# pc_rpi_healthypi.net
KiCad netlist of a schematic drawn in EAGLE
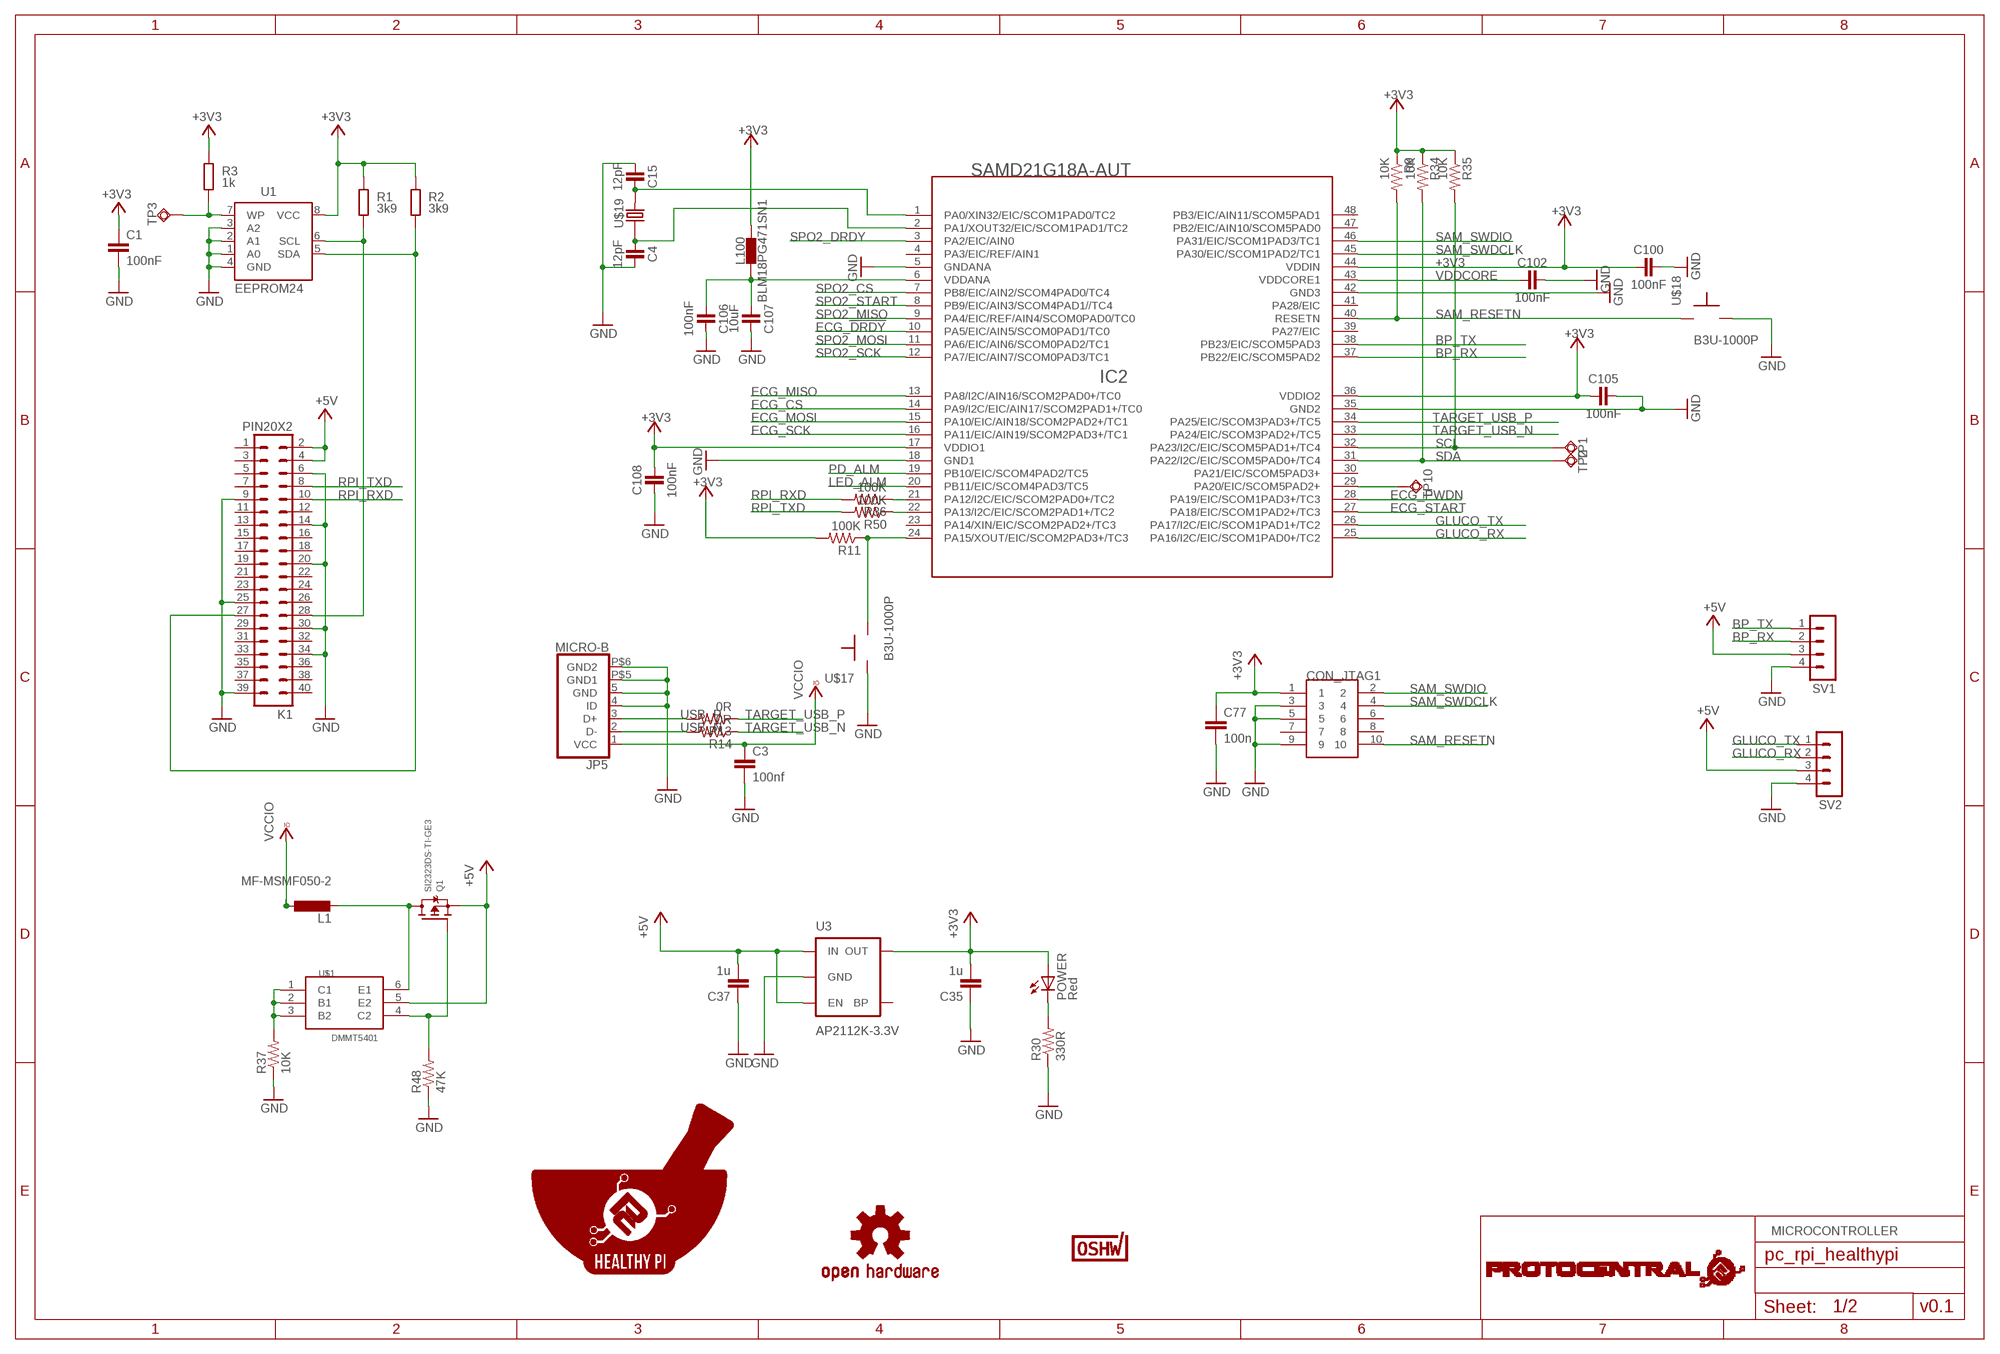
[diagram p0: schematic, sheet 1]
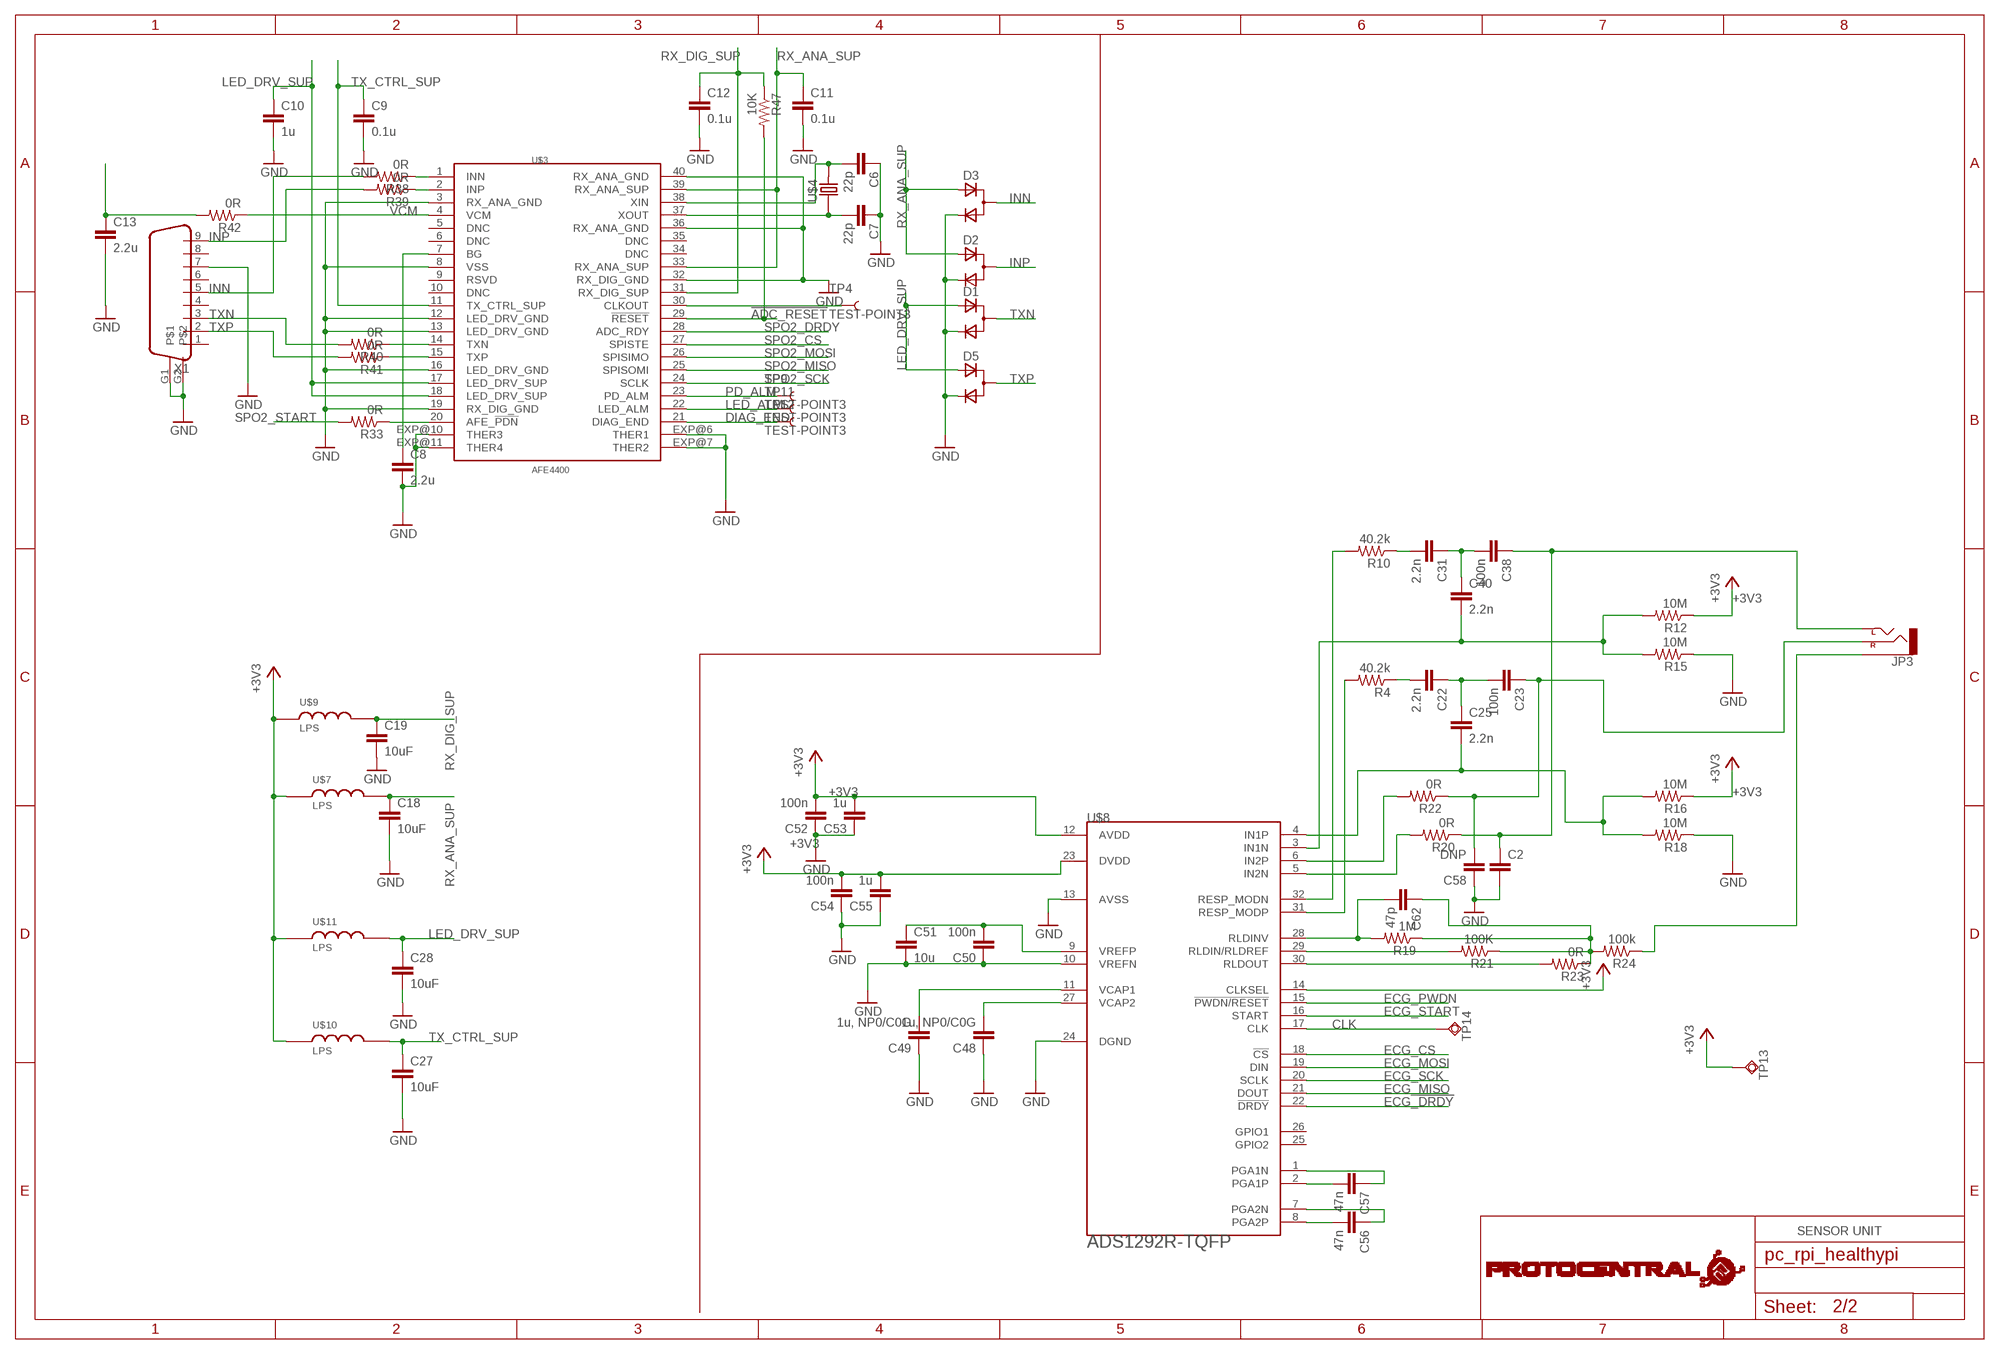
[diagram p1: schematic, sheet 2]

(export (version "E")
  (design (tool "Eeschema 10.0.6"))
  (components
    (comp (ref "C1")
      (value "100nF")
      (footprint "eagle-import:C0805K")
      (libsource (lib "eagle-import") (part "resistor_C-EUC0805K"))
    )
    (comp (ref "C3")
      (value "100nf")
      (footprint "eagle-import:C0402")
      (libsource (lib "eagle-import") (part "C-EUC0402"))
    )
    (comp (ref "C4")
      (value "12pF")
      (footprint "eagle-import:C0402")
      (libsource (lib "eagle-import") (part "CAPACITORS-0402"))
    )
    (comp (ref "C15")
      (value "12pF")
      (footprint "eagle-import:C0402")
      (libsource (lib "eagle-import") (part "CAPACITORS-0402"))
    )
    (comp (ref "C35")
      (value "1u")
      (footprint "eagle-import:C0402")
      (libsource (lib "eagle-import") (part "C-EUC0402"))
    )
    (comp (ref "C37")
      (value "1u")
      (footprint "eagle-import:C0402")
      (libsource (lib "eagle-import") (part "C-EUC0402"))
    )
    (comp (ref "C77")
      (value "100n")
      (footprint "eagle-import:C0805")
      (libsource (lib "eagle-import") (part "C-EUC0805"))
    )
    (comp (ref "C100")
      (value "100nF")
      (footprint "eagle-import:C0805")
      (libsource (lib "eagle-import") (part "CAPACITORS-0805"))
    )
    (comp (ref "C102")
      (value "100nF")
      (footprint "eagle-import:C0805")
      (libsource (lib "eagle-import") (part "CAPACITORS-0805"))
    )
    (comp (ref "C105")
      (value "100nF")
      (footprint "eagle-import:C0805")
      (libsource (lib "eagle-import") (part "CAPACITORS-0805"))
    )
    (comp (ref "C106")
      (value "100nF")
      (footprint "eagle-import:C0805")
      (libsource (lib "eagle-import") (part "CAPACITORS-0805"))
    )
    (comp (ref "C107")
      (value "10uF")
      (footprint "eagle-import:C0805")
      (libsource (lib "eagle-import") (part "CAPACITORS-0805"))
    )
    (comp (ref "C108")
      (value "100nF")
      (footprint "eagle-import:C0805")
      (libsource (lib "eagle-import") (part "CAPACITORS-0805"))
    )
    (comp (ref "CON_JTAG1")
      (value "HDR-SMT-50MIL/5X2")
      (footprint "eagle-import:HDR-SMT-50MIL_5X2")
      (libsource (lib "eagle-import") (part "HDR-SMT-50MIL/5X2"))
    )
    (comp (ref "IC2")
      (value "SAMD21G18A-AUT")
      (footprint "eagle-import:TQFP48")
      (libsource (lib "eagle-import") (part "SAMD21G18A"))
    )
    (comp (ref "JP5")
      (value "MICRO-B")
      (footprint "eagle-import:MICRO-B")
      (libsource (lib "eagle-import") (part "MICRO-B"))
    )
    (comp (ref "K1")
      (value "PIN20X2")
      (footprint "eagle-import:PIN_20X2")
      (libsource (lib "eagle-import") (part "PIN20X2"))
    )
    (comp (ref "L1")
      (value "MF-MSMF050-2")
      (footprint "eagle-import:L1812")
      (libsource (lib "eagle-import") (part "L-EUL1812"))
    )
    (comp (ref "L100")
      (value "BLM18PG471SN1")
      (footprint "eagle-import:C0603")
      (libsource (lib "eagle-import") (part "INDUCTOR-0603"))
    )
    (comp (ref "POWER")
      (value "Red")
      (footprint "eagle-import:CHIPLED_0603")
      (libsource (lib "eagle-import") (part "LEDCHIPLED_0603"))
    )
    (comp (ref "Q1")
      (value "SI2323DS-TI-GE3")
      (footprint "eagle-import:SOT23-R")
      (libsource (lib "eagle-import") (part "MOSFET-P"))
    )
    (comp (ref "R1")
      (value "3k9")
      (footprint "eagle-import:M0805")
      (fields (field (name "TOLERANCE") "5%"))
      (libsource (lib "eagle-import") (part "R-EU_M0805"))
    )
    (comp (ref "R2")
      (value "3k9")
      (footprint "eagle-import:M0805")
      (fields (field (name "TOLERANCE") "5%"))
      (libsource (lib "eagle-import") (part "R-EU_M0805"))
    )
    (comp (ref "R3")
      (value "1k")
      (footprint "eagle-import:M0805")
      (fields (field (name "TOLERANCE") "5%"))
      (libsource (lib "eagle-import") (part "R-EU_M0805"))
    )
    (comp (ref "R9")
      (value "10K")
      (footprint "eagle-import:R0805")
      (libsource (lib "eagle-import") (part "R-US_R0805"))
    )
    (comp (ref "R11")
      (value "100K")
      (footprint "eagle-import:R0805")
      (libsource (lib "eagle-import") (part "R-US_R0805"))
    )
    (comp (ref "R13")
      (value "0R")
      (footprint "eagle-import:R0402")
      (libsource (lib "eagle-import") (part "R-US_R0402"))
    )
    (comp (ref "R14")
      (value "0R")
      (footprint "eagle-import:R0402")
      (libsource (lib "eagle-import") (part "R-US_R0402"))
    )
    (comp (ref "R30")
      (value "330R")
      (footprint "eagle-import:R0402")
      (libsource (lib "eagle-import") (part "R-US_R0402"))
    )
    (comp (ref "R34")
      (value "10K")
      (footprint "eagle-import:R0805")
      (libsource (lib "eagle-import") (part "R-US_R0805"))
    )
    (comp (ref "R35")
      (value "10K")
      (footprint "eagle-import:R0805")
      (libsource (lib "eagle-import") (part "R-US_R0805"))
    )
    (comp (ref "R36")
      (value "100K")
      (footprint "eagle-import:R0402")
      (libsource (lib "eagle-import") (part "R-US_R0402"))
    )
    (comp (ref "R37")
      (value "10K")
      (footprint "eagle-import:R0805")
      (libsource (lib "eagle-import") (part "R-US_R0805"))
    )
    (comp (ref "R48")
      (value "47K")
      (footprint "eagle-import:R0805")
      (libsource (lib "eagle-import") (part "R-US_R0805"))
    )
    (comp (ref "R50")
      (value "100K")
      (footprint "eagle-import:R0402")
      (libsource (lib "eagle-import") (part "R-US_R0402"))
    )
    (comp (ref "SV1")
      (value "MA04-1")
      (footprint "eagle-import:MA04-1")
      (libsource (lib "eagle-import") (part "MA04-1"))
    )
    (comp (ref "SV2")
      (value "MA04-1")
      (footprint "eagle-import:MA04-1")
      (libsource (lib "eagle-import") (part "MA04-1"))
    )
    (comp (ref "TP1")
      (value "TPSQB1,27")
      (footprint "eagle-import:B1,27")
      (libsource (lib "eagle-import") (part "TPSQB1,27"))
    )
    (comp (ref "TP2")
      (value "TPSQB1,27")
      (footprint "eagle-import:B1,27")
      (libsource (lib "eagle-import") (part "TPSQB1,27"))
    )
    (comp (ref "TP3")
      (value "TPSQB1,27")
      (footprint "eagle-import:B1,27")
      (libsource (lib "eagle-import") (part "TPSQB1,27"))
    )
    (comp (ref "TP10")
      (value "TPSQB1,27")
      (footprint "eagle-import:B1,27")
      (libsource (lib "eagle-import") (part "TPSQB1,27"))
    )
    (comp (ref "U$1")
      (value "DMMT5401")
      (footprint "eagle-import:SOT26")
      (libsource (lib "eagle-import") (part "DMMT5401"))
    )
    (comp (ref "U$5")
      (value "OSHW-LOGOM")
      (footprint "eagle-import:OSHW-LOGO-M")
      (libsource (lib "eagle-import") (part "OSHW-LOGOM"))
    )
    (comp (ref "U$6")
      (value "PROTY_LOGO_WITH_TEXT")
      (footprint "eagle-import:PROTY_WITH_TEXT")
      (libsource (lib "eagle-import") (part "PROTY_LOGO_WITH_TEXT"))
    )
    (comp (ref "U$13")
      (value "CERT-SMALL")
      (footprint "eagle-import:CERT-SMALL-SILK")
      (libsource (lib "eagle-import") (part "CERT-SMALL"))
    )
    (comp (ref "U$15")
      (value "HEALTHYPI")
      (footprint "eagle-import:HEALTHYPI")
      (libsource (lib "eagle-import") (part "HEALTHYPI"))
    )
    (comp (ref "U$17")
      (value "B3U-1000P")
      (footprint "eagle-import:B3U-1000P")
      (libsource (lib "eagle-import") (part "B3U-1000P"))
    )
    (comp (ref "U$18")
      (value "B3U-1000P")
      (footprint "eagle-import:B3U-1000P")
      (libsource (lib "eagle-import") (part "B3U-1000P"))
    )
    (comp (ref "U$19")
      (value "ECS-X-34B")
      (footprint "eagle-import:ECX-31B")
      (libsource (lib "eagle-import") (part "ECS-X-34B"))
    )
    (comp (ref "U1")
      (value "EEPROM24")
      (footprint "eagle-import:SOIC8")
      (libsource (lib "eagle-import") (part "EEPROM24"))
    )
    (comp (ref "U3")
      (value "AP2112K-3.3V")
      (footprint "eagle-import:SOT23-5")
      (libsource (lib "eagle-import") (part "V_REG_LDOSMD"))
    )
    (comp (ref "C2")
      (value "C-EUC0402")
      (footprint "eagle-import:C0402")
      (libsource (lib "eagle-import") (part "C-EUC0402"))
    )
    (comp (ref "C6")
      (value "22p")
      (footprint "eagle-import:C0402")
      (libsource (lib "eagle-import") (part "C-EUC0402"))
    )
    (comp (ref "C7")
      (value "22p")
      (footprint "eagle-import:C0402")
      (libsource (lib "eagle-import") (part "C-EUC0402"))
    )
    (comp (ref "C8")
      (value "2.2u")
      (footprint "eagle-import:C0402")
      (libsource (lib "eagle-import") (part "C-EUC0402"))
    )
    (comp (ref "C9")
      (value "0.1u")
      (footprint "eagle-import:C0402")
      (libsource (lib "eagle-import") (part "C-EUC0402"))
    )
    (comp (ref "C10")
      (value "1u")
      (footprint "eagle-import:C0805")
      (libsource (lib "eagle-import") (part "C-EUC0805"))
    )
    (comp (ref "C11")
      (value "0.1u")
      (footprint "eagle-import:C0402")
      (libsource (lib "eagle-import") (part "C-EUC0402"))
    )
    (comp (ref "C12")
      (value "0.1u")
      (footprint "eagle-import:C0402")
      (libsource (lib "eagle-import") (part "C-EUC0402"))
    )
    (comp (ref "C13")
      (value "2.2u")
      (footprint "eagle-import:C0402")
      (libsource (lib "eagle-import") (part "C-EUC0402"))
    )
    (comp (ref "C18")
      (value "10uF")
      (footprint "eagle-import:C0805")
      (libsource (lib "eagle-import") (part "C-EUC0805"))
    )
    (comp (ref "C19")
      (value "10uF")
      (footprint "eagle-import:C0805")
      (libsource (lib "eagle-import") (part "C-EUC0805"))
    )
    (comp (ref "C22")
      (value "2.2n")
      (footprint "eagle-import:C0402")
      (libsource (lib "eagle-import") (part "C-EUC0402"))
    )
    (comp (ref "C23")
      (value "100n")
      (footprint "eagle-import:C0402")
      (libsource (lib "eagle-import") (part "C-EUC0402"))
    )
    (comp (ref "C25")
      (value "2.2n")
      (footprint "eagle-import:C0402")
      (libsource (lib "eagle-import") (part "C-EUC0402"))
    )
    (comp (ref "C27")
      (value "10uF")
      (footprint "eagle-import:C0805")
      (libsource (lib "eagle-import") (part "C-EUC0805"))
    )
    (comp (ref "C28")
      (value "10uF")
      (footprint "eagle-import:C0805")
      (libsource (lib "eagle-import") (part "C-EUC0805"))
    )
    (comp (ref "C31")
      (value "2.2n")
      (footprint "eagle-import:C0402")
      (libsource (lib "eagle-import") (part "C-EUC0402"))
    )
    (comp (ref "C38")
      (value "100n")
      (footprint "eagle-import:C0402")
      (libsource (lib "eagle-import") (part "C-EUC0402"))
    )
    (comp (ref "C40")
      (value "2.2n")
      (footprint "eagle-import:C0402")
      (libsource (lib "eagle-import") (part "C-EUC0402"))
    )
    (comp (ref "C48")
      (value "1u, NP0/C0G")
      (footprint "eagle-import:C0402")
      (libsource (lib "eagle-import") (part "C-EUC0402"))
    )
    (comp (ref "C49")
      (value "1u, NP0/C0G")
      (footprint "eagle-import:C0402")
      (libsource (lib "eagle-import") (part "C-EUC0402"))
    )
    (comp (ref "C50")
      (value "100n")
      (footprint "eagle-import:C0402")
      (libsource (lib "eagle-import") (part "C-EUC0402"))
    )
    (comp (ref "C51")
      (value "10u")
      (footprint "eagle-import:C0603")
      (libsource (lib "eagle-import") (part "resistor_C-EUC0603"))
    )
    (comp (ref "C52")
      (value "100n")
      (footprint "eagle-import:C0402")
      (libsource (lib "eagle-import") (part "C-EUC0402"))
    )
    (comp (ref "C53")
      (value "1u")
      (footprint "eagle-import:C0402")
      (libsource (lib "eagle-import") (part "C-EUC0402"))
    )
    (comp (ref "C54")
      (value "100n")
      (footprint "eagle-import:C0402")
      (libsource (lib "eagle-import") (part "C-EUC0402"))
    )
    (comp (ref "C55")
      (value "1u")
      (footprint "eagle-import:C0402")
      (libsource (lib "eagle-import") (part "C-EUC0402"))
    )
    (comp (ref "C56")
      (value "47n")
      (footprint "eagle-import:C0402")
      (libsource (lib "eagle-import") (part "C-EUC0402"))
    )
    (comp (ref "C57")
      (value "47n")
      (footprint "eagle-import:C0402")
      (libsource (lib "eagle-import") (part "C-EUC0402"))
    )
    (comp (ref "C58")
      (value "DNP")
      (footprint "eagle-import:C0402")
      (libsource (lib "eagle-import") (part "C-EUC0402"))
    )
    (comp (ref "C62")
      (value "47p")
      (footprint "eagle-import:C0402")
      (libsource (lib "eagle-import") (part "C-EUC0402"))
    )
    (comp (ref "D1")
      (value "D_ACACSOT323")
      (footprint "eagle-import:SOT323")
      (libsource (lib "eagle-import") (part "D_ACACSOT323"))
    )
    (comp (ref "D2")
      (value "D_ACACSOT323")
      (footprint "eagle-import:SOT323")
      (libsource (lib "eagle-import") (part "D_ACACSOT323"))
    )
    (comp (ref "D3")
      (value "D_ACACSOT323")
      (footprint "eagle-import:SOT323")
      (libsource (lib "eagle-import") (part "D_ACACSOT323"))
    )
    (comp (ref "D5")
      (value "D_ACACSOT323")
      (footprint "eagle-import:SOT323")
      (libsource (lib "eagle-import") (part "D_ACACSOT323"))
    )
    (comp (ref "JP3")
      (value "AUDIO-JACKSMD2")
      (footprint "eagle-import:AUDIO-JACK-3.5MM-SMD")
      (libsource (lib "eagle-import") (part "AUDIO-JACKSMD2"))
    )
    (comp (ref "R4")
      (value "40.2k")
      (footprint "eagle-import:R0402")
      (libsource (lib "eagle-import") (part "R-US_R0402"))
    )
    (comp (ref "R10")
      (value "40.2k")
      (footprint "eagle-import:R0402")
      (libsource (lib "eagle-import") (part "R-US_R0402"))
    )
    (comp (ref "R12")
      (value "10M")
      (footprint "eagle-import:R0402")
      (libsource (lib "eagle-import") (part "R-US_R0402"))
    )
    (comp (ref "R15")
      (value "10M")
      (footprint "eagle-import:R0402")
      (libsource (lib "eagle-import") (part "R-US_R0402"))
    )
    (comp (ref "R16")
      (value "10M")
      (footprint "eagle-import:R0402")
      (libsource (lib "eagle-import") (part "R-US_R0402"))
    )
    (comp (ref "R18")
      (value "10M")
      (footprint "eagle-import:R0402")
      (libsource (lib "eagle-import") (part "R-US_R0402"))
    )
    (comp (ref "R19")
      (value "1M")
      (footprint "eagle-import:R0402")
      (libsource (lib "eagle-import") (part "R-US_R0402"))
    )
    (comp (ref "R20")
      (value "0R")
      (footprint "eagle-import:R0402")
      (libsource (lib "eagle-import") (part "R-US_R0402"))
    )
    (comp (ref "R21")
      (value "100K")
      (footprint "eagle-import:R0402")
      (libsource (lib "eagle-import") (part "R-US_R0402"))
    )
    (comp (ref "R22")
      (value "0R")
      (footprint "eagle-import:R0402")
      (libsource (lib "eagle-import") (part "R-US_R0402"))
    )
    (comp (ref "R23")
      (value "0R")
      (footprint "eagle-import:R0402")
      (libsource (lib "eagle-import") (part "R-US_R0402"))
    )
    (comp (ref "R24")
      (value "100k")
      (footprint "eagle-import:R0402")
      (libsource (lib "eagle-import") (part "R-US_R0402"))
    )
    (comp (ref "R33")
      (value "0R")
      (footprint "eagle-import:R0402")
      (libsource (lib "eagle-import") (part "R-US_R0402"))
    )
    (comp (ref "R38")
      (value "0R")
      (footprint "eagle-import:R0402")
      (libsource (lib "eagle-import") (part "R-US_R0402"))
    )
    (comp (ref "R39")
      (value "0R")
      (footprint "eagle-import:R0402")
      (libsource (lib "eagle-import") (part "R-US_R0402"))
    )
    (comp (ref "R40")
      (value "0R")
      (footprint "eagle-import:R0402")
      (libsource (lib "eagle-import") (part "R-US_R0402"))
    )
    (comp (ref "R41")
      (value "0R")
      (footprint "eagle-import:R0402")
      (libsource (lib "eagle-import") (part "R-US_R0402"))
    )
    (comp (ref "R42")
      (value "0R")
      (footprint "eagle-import:R0402")
      (libsource (lib "eagle-import") (part "R-US_R0402"))
    )
    (comp (ref "R47")
      (value "10K")
      (footprint "eagle-import:R0402")
      (libsource (lib "eagle-import") (part "R-US_R0402"))
    )
    (comp (ref "TP4")
      (value "TEST-POINT3")
      (footprint "eagle-import:PAD.03X.03")
      (libsource (lib "eagle-import") (part "TEST-POINT3"))
    )
    (comp (ref "TP9")
      (value "TEST-POINT3")
      (footprint "eagle-import:PAD.03X.03")
      (libsource (lib "eagle-import") (part "TEST-POINT3"))
    )
    (comp (ref "TP11")
      (value "TEST-POINT3")
      (footprint "eagle-import:PAD.03X.03")
      (libsource (lib "eagle-import") (part "TEST-POINT3"))
    )
    (comp (ref "TP12")
      (value "TEST-POINT3")
      (footprint "eagle-import:PAD.03X.03")
      (libsource (lib "eagle-import") (part "TEST-POINT3"))
    )
    (comp (ref "TP13")
      (value "TPSQB1,27")
      (footprint "eagle-import:B1,27")
      (libsource (lib "eagle-import") (part "TPSQB1,27"))
    )
    (comp (ref "TP14")
      (value "TPSQB1,27")
      (footprint "eagle-import:B1,27")
      (libsource (lib "eagle-import") (part "TPSQB1,27"))
    )
    (comp (ref "U$2")
      (value "PROTY_LOGO_WITH_TEXT")
      (footprint "eagle-import:PROTY_WITH_TEXT")
      (libsource (lib "eagle-import") (part "PROTY_LOGO_WITH_TEXT"))
    )
    (comp (ref "U$3")
      (value "AFE4400")
      (footprint "eagle-import:QFN-40")
      (libsource (lib "eagle-import") (part "AFE4400"))
    )
    (comp (ref "U$4")
      (value "ABM3")
      (footprint "eagle-import:ABM3")
      (libsource (lib "eagle-import") (part "ABM3"))
    )
    (comp (ref "U$7")
      (value "LPS")
      (footprint "eagle-import:LPS")
      (libsource (lib "eagle-import") (part "LPS"))
    )
    (comp (ref "U$8")
      (value "ADS1292R-TQFP")
      (footprint "eagle-import:SQFP-S-5X5-32")
      (libsource (lib "eagle-import") (part "ADS1292R-TQFP"))
    )
    (comp (ref "U$9")
      (value "LPS")
      (footprint "eagle-import:LPS")
      (libsource (lib "eagle-import") (part "LPS"))
    )
    (comp (ref "U$10")
      (value "LPS")
      (footprint "eagle-import:LPS")
      (libsource (lib "eagle-import") (part "LPS"))
    )
    (comp (ref "U$11")
      (value "LPS")
      (footprint "eagle-import:LPS")
      (libsource (lib "eagle-import") (part "LPS"))
    )
    (comp (ref "X1")
      (value "DB9")
      (footprint "eagle-import:DB9")
      (libsource (lib "eagle-import") (part "DB9"))
    )
  )
  (nets
    (net (code "1") (name "+3V3") (class "Default")
      (node (ref "C1") (pin "1") (pinfunction "1_1") (pintype "passive"))
      (node (ref "C100") (pin "1") (pinfunction "1_1") (pintype "passive"))
      (node (ref "C105") (pin "1") (pinfunction "1_1") (pintype "passive"))
      (node (ref "C108") (pin "2") (pinfunction "2_2") (pintype "passive"))
      (node (ref "C35") (pin "2") (pinfunction "2_2") (pintype "passive"))
      (node (ref "C52") (pin "2") (pinfunction "2_2") (pintype "passive"))
      (node (ref "C53") (pin "2") (pinfunction "2_2") (pintype "passive"))
      (node (ref "C54") (pin "2") (pinfunction "2_2") (pintype "passive"))
      (node (ref "C55") (pin "2") (pinfunction "2_2") (pintype "passive"))
      (node (ref "C77") (pin "1") (pinfunction "1_1") (pintype "passive"))
      (node (ref "CON_JTAG1") (pin "1") (pinfunction "1_1") (pintype "bidirectional"))
      (node (ref "IC2") (pin "17") (pinfunction "VDDIO1_17") (pintype "power_in"))
      (node (ref "IC2") (pin "36") (pinfunction "VDDIO2_36") (pintype "power_in"))
      (node (ref "IC2") (pin "44") (pinfunction "VDDIN_44") (pintype "power_in"))
      (node (ref "L100") (pin "2") (pinfunction "2_2") (pintype "passive"))
      (node (ref "POWER") (pin "A") (pinfunction "A_A") (pintype "passive"))
      (node (ref "R1") (pin "2") (pinfunction "2_2") (pintype "passive"))
      (node (ref "R11") (pin "2") (pinfunction "2_2") (pintype "passive"))
      (node (ref "R12") (pin "1") (pinfunction "1_1") (pintype "passive"))
      (node (ref "R16") (pin "1") (pinfunction "1_1") (pintype "passive"))
      (node (ref "R2") (pin "2") (pinfunction "2_2") (pintype "passive"))
      (node (ref "R3") (pin "2") (pinfunction "2_2") (pintype "passive"))
      (node (ref "R34") (pin "1") (pinfunction "1_1") (pintype "passive"))
      (node (ref "R35") (pin "1") (pinfunction "1_1") (pintype "passive"))
      (node (ref "R9") (pin "1") (pinfunction "1_1") (pintype "passive"))
      (node (ref "TP13") (pin "TP") (pinfunction "TP_TP") (pintype "input"))
      (node (ref "U$10") (pin "1") (pinfunction "P$1_1") (pintype "bidirectional"))
      (node (ref "U$11") (pin "1") (pinfunction "P$1_1") (pintype "bidirectional"))
      (node (ref "U$7") (pin "1") (pinfunction "P$1_1") (pintype "bidirectional"))
      (node (ref "U$8") (pin "12") (pinfunction "AVDD_12") (pintype "power_in"))
      (node (ref "U$8") (pin "14") (pinfunction "CLKSEL_14") (pintype "bidirectional"))
      (node (ref "U$8") (pin "23") (pinfunction "DVDD_23") (pintype "power_in"))
      (node (ref "U$9") (pin "1") (pinfunction "P$1_1") (pintype "bidirectional"))
      (node (ref "U1") (pin "8") (pinfunction "VCC_8") (pintype "power_in"))
      (node (ref "U3") (pin "5") (pinfunction "OUT_5") (pintype "passive"))
    )
    (net (code "2") (name "+5V") (class "Default")
      (node (ref "C37") (pin "2") (pinfunction "2_2") (pintype "passive"))
      (node (ref "K1") (pin "2") (pinfunction "2_2") (pintype "passive"))
      (node (ref "K1") (pin "4") (pinfunction "4_4") (pintype "passive"))
      (node (ref "Q1") (pin "2") (pinfunction "S_2") (pintype "passive"))
      (node (ref "SV1") (pin "3") (pinfunction "3_3") (pintype "passive"))
      (node (ref "SV2") (pin "3") (pinfunction "3_3") (pintype "passive"))
      (node (ref "U$1") (pin "5") (pinfunction "E2_5") (pintype "bidirectional"))
      (node (ref "U3") (pin "1") (pinfunction "IN_1") (pintype "input"))
      (node (ref "U3") (pin "3") (pinfunction "EN_3") (pintype "input"))
    )
    (net (code "3") (name "BP_RX") (class "Default")
      (node (ref "IC2") (pin "37") (pinfunction "PB22/EIC/SCOM5PAD2_37") (pintype "bidirectional"))
      (node (ref "SV1") (pin "2") (pinfunction "2_2") (pintype "passive"))
    )
    (net (code "4") (name "BP_TX") (class "Default")
      (node (ref "IC2") (pin "38") (pinfunction "PB23/EIC/SCOM5PAD3_38") (pintype "bidirectional"))
      (node (ref "SV1") (pin "1") (pinfunction "1_1") (pintype "passive"))
    )
    (net (code "5") (name "CLK") (class "Default")
      (node (ref "TP14") (pin "TP") (pinfunction "TP_TP") (pintype "input"))
      (node (ref "U$8") (pin "17") (pinfunction "CLK_17") (pintype "bidirectional"))
    )
    (net (code "6") (name "DIAG_END") (class "Default")
      (node (ref "TP12") (pin "P$1") (pinfunction "1_P$1") (pintype "bidirectional"))
      (node (ref "U$3") (pin "21") (pinfunction "DIAG_END_21") (pintype "bidirectional"))
    )
    (net (code "7") (name "ECG_CS") (class "Default")
      (node (ref "IC2") (pin "14") (pinfunction "PA9/I2C/EIC/AIN17/SCOM2PAD1+/TC0_14") (pintype "bidirectional"))
      (node (ref "U$8") (pin "18") (pinfunction "~{CS}_18") (pintype "bidirectional"))
    )
    (net (code "8") (name "ECG_MISO") (class "Default")
      (node (ref "IC2") (pin "13") (pinfunction "PA8/I2C/AIN16/SCOM2PAD0+/TC0_13") (pintype "bidirectional"))
      (node (ref "U$8") (pin "21") (pinfunction "DOUT_21") (pintype "bidirectional"))
    )
    (net (code "9") (name "ECG_MOSI") (class "Default")
      (node (ref "IC2") (pin "15") (pinfunction "PA10/EIC/AIN18/SCOM2PAD2+/TC1_15") (pintype "bidirectional"))
      (node (ref "U$8") (pin "19") (pinfunction "DIN_19") (pintype "bidirectional"))
    )
    (net (code "10") (name "ECG_PWDN") (class "Default")
      (node (ref "IC2") (pin "28") (pinfunction "PA19/EIC/SCOM1PAD3+/TC3_28") (pintype "bidirectional"))
      (node (ref "U$8") (pin "15") (pinfunction "~{PWDN/RESET}_15") (pintype "bidirectional"))
    )
    (net (code "11") (name "ECG_SCK") (class "Default")
      (node (ref "IC2") (pin "16") (pinfunction "PA11/EIC/AIN19/SCOM2PAD3+/TC1_16") (pintype "bidirectional"))
      (node (ref "U$8") (pin "20") (pinfunction "SCLK_20") (pintype "bidirectional"))
    )
    (net (code "12") (name "ECG_START") (class "Default")
      (node (ref "IC2") (pin "27") (pinfunction "PA18/EIC/SCOM1PAD2+/TC3_27") (pintype "bidirectional"))
      (node (ref "U$8") (pin "16") (pinfunction "START_16") (pintype "bidirectional"))
    )
    (net (code "13") (name "ECG_~{DRDY}") (class "Default")
      (node (ref "IC2") (pin "10") (pinfunction "PA5/EIC/AIN5/SCOM0PAD1/TC0_10") (pintype "bidirectional"))
      (node (ref "U$8") (pin "22") (pinfunction "~{DRDY}_22") (pintype "bidirectional"))
    )
    (net (code "14") (name "GLUCO_RX") (class "Default")
      (node (ref "IC2") (pin "25") (pinfunction "PA16/I2C/EIC/SCOM1PAD0+/TC2_25") (pintype "bidirectional"))
      (node (ref "SV2") (pin "2") (pinfunction "2_2") (pintype "passive"))
    )
    (net (code "15") (name "GLUCO_TX") (class "Default")
      (node (ref "IC2") (pin "26") (pinfunction "PA17/I2C/EIC/SCOM1PAD1+/TC2_26") (pintype "bidirectional"))
      (node (ref "SV2") (pin "1") (pinfunction "1_1") (pintype "passive"))
    )
    (net (code "16") (name "GND") (class "Default")
      (node (ref "C1") (pin "2") (pinfunction "2_2") (pintype "passive"))
      (node (ref "C10") (pin "2") (pinfunction "2_2") (pintype "passive"))
      (node (ref "C100") (pin "2") (pinfunction "2_2") (pintype "passive"))
      (node (ref "C102") (pin "2") (pinfunction "2_2") (pintype "passive"))
      (node (ref "C105") (pin "2") (pinfunction "2_2") (pintype "passive"))
      (node (ref "C106") (pin "2") (pinfunction "2_2") (pintype "passive"))
      (node (ref "C107") (pin "2") (pinfunction "2_2") (pintype "passive"))
      (node (ref "C108") (pin "1") (pinfunction "1_1") (pintype "passive"))
      (node (ref "C11") (pin "2") (pinfunction "2_2") (pintype "passive"))
      (node (ref "C12") (pin "2") (pinfunction "2_2") (pintype "passive"))
      (node (ref "C13") (pin "2") (pinfunction "2_2") (pintype "passive"))
      (node (ref "C15") (pin "1") (pinfunction "1_1") (pintype "passive"))
      (node (ref "C18") (pin "2") (pinfunction "2_2") (pintype "passive"))
      (node (ref "C19") (pin "2") (pinfunction "2_2") (pintype "passive"))
      (node (ref "C2") (pin "2") (pinfunction "2_2") (pintype "passive"))
      (node (ref "C27") (pin "2") (pinfunction "2_2") (pintype "passive"))
      (node (ref "C28") (pin "2") (pinfunction "2_2") (pintype "passive"))
      (node (ref "C3") (pin "2") (pinfunction "2_2") (pintype "passive"))
      (node (ref "C35") (pin "1") (pinfunction "1_1") (pintype "passive"))
      (node (ref "C37") (pin "1") (pinfunction "1_1") (pintype "passive"))
      (node (ref "C4") (pin "2") (pinfunction "2_2") (pintype "passive"))
      (node (ref "C48") (pin "1") (pinfunction "1_1") (pintype "passive"))
      (node (ref "C49") (pin "1") (pinfunction "1_1") (pintype "passive"))
      (node (ref "C50") (pin "1") (pinfunction "1_1") (pintype "passive"))
      (node (ref "C51") (pin "2") (pinfunction "2_2") (pintype "passive"))
      (node (ref "C52") (pin "1") (pinfunction "1_1") (pintype "passive"))
      (node (ref "C53") (pin "1") (pinfunction "1_1") (pintype "passive"))
      (node (ref "C54") (pin "1") (pinfunction "1_1") (pintype "passive"))
      (node (ref "C55") (pin "1") (pinfunction "1_1") (pintype "passive"))
      (node (ref "C58") (pin "1") (pinfunction "1_1") (pintype "passive"))
      (node (ref "C6") (pin "1") (pinfunction "1_1") (pintype "passive"))
      (node (ref "C7") (pin "1") (pinfunction "1_1") (pintype "passive"))
      (node (ref "C77") (pin "2") (pinfunction "2_2") (pintype "passive"))
      (node (ref "C8") (pin "2") (pinfunction "2_2") (pintype "passive"))
      (node (ref "C9") (pin "2") (pinfunction "2_2") (pintype "passive"))
      (node (ref "CON_JTAG1") (pin "3") (pinfunction "3_3") (pintype "bidirectional"))
      (node (ref "CON_JTAG1") (pin "5") (pinfunction "5_5") (pintype "bidirectional"))
      (node (ref "CON_JTAG1") (pin "9") (pinfunction "9_9") (pintype "bidirectional"))
      (node (ref "D1") (pin "2") (pinfunction "C_2") (pintype "passive"))
      (node (ref "D2") (pin "2") (pinfunction "C_2") (pintype "passive"))
      (node (ref "D3") (pin "2") (pinfunction "C_2") (pintype "passive"))
      (node (ref "D5") (pin "2") (pinfunction "C_2") (pintype "passive"))
      (node (ref "IC2") (pin "18") (pinfunction "GND1_18") (pintype "power_in"))
      (node (ref "IC2") (pin "35") (pinfunction "GND2_35") (pintype "power_in"))
      (node (ref "IC2") (pin "42") (pinfunction "GND3_42") (pintype "power_in"))
      (node (ref "IC2") (pin "5") (pinfunction "GNDANA_5") (pintype "power_in"))
      (node (ref "JP5") (pin "4") (pinfunction "ID_4") (pintype "bidirectional"))
      (node (ref "JP5") (pin "5") (pinfunction "GND_5") (pintype "bidirectional"))
      (node (ref "JP5") (pin "P$5") (pinfunction "GND1_P$5") (pintype "bidirectional"))
      (node (ref "JP5") (pin "P$6") (pinfunction "GND2_P$6") (pintype "bidirectional"))
      (node (ref "K1") (pin "14") (pinfunction "14_14") (pintype "passive"))
      (node (ref "K1") (pin "20") (pinfunction "20_20") (pintype "passive"))
      (node (ref "K1") (pin "25") (pinfunction "25_25") (pintype "passive"))
      (node (ref "K1") (pin "30") (pinfunction "30_30") (pintype "passive"))
      (node (ref "K1") (pin "34") (pinfunction "34_34") (pintype "passive"))
      (node (ref "K1") (pin "39") (pinfunction "39_39") (pintype "passive"))
      (node (ref "K1") (pin "6") (pinfunction "6_6") (pintype "passive"))
      (node (ref "K1") (pin "9") (pinfunction "9_9") (pintype "passive"))
      (node (ref "R15") (pin "1") (pinfunction "1_1") (pintype "passive"))
      (node (ref "R18") (pin "1") (pinfunction "1_1") (pintype "passive"))
      (node (ref "R30") (pin "1") (pinfunction "1_1") (pintype "passive"))
      (node (ref "R37") (pin "1") (pinfunction "1_1") (pintype "passive"))
      (node (ref "R48") (pin "1") (pinfunction "1_1") (pintype "passive"))
      (node (ref "SV1") (pin "4") (pinfunction "4_4") (pintype "passive"))
      (node (ref "SV2") (pin "4") (pinfunction "4_4") (pintype "passive"))
      (node (ref "U$17") (pin "P$1") (pinfunction "P$1_P$1") (pintype "bidirectional"))
      (node (ref "U$18") (pin "P$2") (pinfunction "P$2_P$2") (pintype "bidirectional"))
      (node (ref "U$3") (pin "12") (pinfunction "LED_DRV_GND_12") (pintype "bidirectional"))
      (node (ref "U$3") (pin "13") (pinfunction "LED_DRV_GND_13") (pintype "bidirectional"))
      (node (ref "U$3") (pin "16") (pinfunction "LED_DRV_GND_16") (pintype "bidirectional"))
      (node (ref "U$3") (pin "19") (pinfunction "RX_DIG_GND_19") (pintype "bidirectional"))
      (node (ref "U$3") (pin "3") (pinfunction "RX_ANA_GND_3") (pintype "bidirectional"))
      (node (ref "U$3") (pin "32") (pinfunction "RX_DIG_GND_32") (pintype "bidirectional"))
      (node (ref "U$3") (pin "36") (pinfunction "RX_ANA_GND_36") (pintype "bidirectional"))
      (node (ref "U$3") (pin "40") (pinfunction "RX_ANA_GND_40") (pintype "bidirectional"))
      (node (ref "U$3") (pin "8") (pinfunction "VSS_8") (pintype "bidirectional"))
      (node (ref "U$3") (pin "EXP@10") (pinfunction "THER3_EXP@10") (pintype "bidirectional"))
      (node (ref "U$3") (pin "EXP@11") (pinfunction "THER4_EXP@11") (pintype "bidirectional"))
      (node (ref "U$3") (pin "EXP@6") (pinfunction "THER1_EXP@6") (pintype "bidirectional"))
      (node (ref "U$3") (pin "EXP@7") (pinfunction "THER2_EXP@7") (pintype "bidirectional"))
      (node (ref "U$8") (pin "10") (pinfunction "VREFN_10") (pintype "bidirectional"))
      (node (ref "U$8") (pin "13") (pinfunction "AVSS_13") (pintype "bidirectional"))
      (node (ref "U$8") (pin "24") (pinfunction "DGND_24") (pintype "bidirectional"))
      (node (ref "U1") (pin "1") (pinfunction "A0_1") (pintype "input"))
      (node (ref "U1") (pin "2") (pinfunction "A1_2") (pintype "input"))
      (node (ref "U1") (pin "3") (pinfunction "A2_3") (pintype "input"))
      (node (ref "U1") (pin "4") (pinfunction "GND_4") (pintype "power_in"))
      (node (ref "U3") (pin "2") (pinfunction "GND_2") (pintype "input"))
      (node (ref "X1") (pin "7") (pinfunction "7_7") (pintype "passive"))
      (node (ref "X1") (pin "G1") (pinfunction "P$1_G1") (pintype "bidirectional"))
      (node (ref "X1") (pin "G2") (pinfunction "P$2_G2") (pintype "bidirectional"))
    )
    (net (code "17") (name "INN") (class "Default")
      (node (ref "D3") (pin "1") (pinfunction "CA_1") (pintype "passive"))
      (node (ref "R38") (pin "2") (pinfunction "2_2") (pintype "passive"))
      (node (ref "X1") (pin "5") (pinfunction "5_5") (pintype "passive"))
    )
    (net (code "18") (name "INP") (class "Default")
      (node (ref "D2") (pin "1") (pinfunction "CA_1") (pintype "passive"))
      (node (ref "R39") (pin "2") (pinfunction "2_2") (pintype "passive"))
      (node (ref "X1") (pin "9") (pinfunction "9_9") (pintype "passive"))
    )
    (net (code "19") (name "LED_ALM") (class "Default")
      (node (ref "IC2") (pin "20") (pinfunction "PB11/EIC/SCOM4PAD3/TC5_20") (pintype "bidirectional"))
      (node (ref "TP11") (pin "P$1") (pinfunction "1_P$1") (pintype "bidirectional"))
      (node (ref "U$3") (pin "22") (pinfunction "LED_ALM_22") (pintype "bidirectional"))
    )
    (net (code "20") (name "LED_DRV_SUP") (class "Default")
      (node (ref "C10") (pin "1") (pinfunction "1_1") (pintype "passive"))
      (node (ref "C28") (pin "1") (pinfunction "1_1") (pintype "passive"))
      (node (ref "D1") (pin "3") (pinfunction "A_3") (pintype "passive"))
      (node (ref "D5") (pin "3") (pinfunction "A_3") (pintype "passive"))
      (node (ref "U$11") (pin "2") (pinfunction "P$2_2") (pintype "bidirectional"))
      (node (ref "U$3") (pin "17") (pinfunction "LED_DRV_SUP_17") (pintype "bidirectional"))
      (node (ref "U$3") (pin "18") (pinfunction "LED_DRV_SUP_18") (pintype "bidirectional"))
    )
    (net (code "21") (name "Net-(C13-Pad1)") (class "Default")
      (node (ref "C13") (pin "1") (pinfunction "1_1") (pintype "passive"))
      (node (ref "R42") (pin "2") (pinfunction "2_2") (pintype "passive"))
    )
    (net (code "22") (name "Net-(C22-Pad1)") (class "Default")
      (node (ref "C22") (pin "1") (pinfunction "1_1") (pintype "passive"))
      (node (ref "C23") (pin "2") (pinfunction "2_2") (pintype "passive"))
      (node (ref "C25") (pin "1") (pinfunction "1_1") (pintype "passive"))
    )
    (net (code "23") (name "Net-(C22-Pad2)") (class "Default")
      (node (ref "C22") (pin "2") (pinfunction "2_2") (pintype "passive"))
      (node (ref "R4") (pin "1") (pinfunction "1_1") (pintype "passive"))
    )
    (net (code "24") (name "Net-(C31-Pad1)") (class "Default")
      (node (ref "C31") (pin "1") (pinfunction "1_1") (pintype "passive"))
      (node (ref "C38") (pin "2") (pinfunction "2_2") (pintype "passive"))
      (node (ref "C40") (pin "1") (pinfunction "1_1") (pintype "passive"))
    )
    (net (code "25") (name "Net-(C31-Pad2)") (class "Default")
      (node (ref "C31") (pin "2") (pinfunction "2_2") (pintype "passive"))
      (node (ref "R10") (pin "1") (pinfunction "1_1") (pintype "passive"))
    )
    (net (code "26") (name "Net-(C62-Pad1)") (class "Default")
      (node (ref "C62") (pin "1") (pinfunction "1_1") (pintype "passive"))
      (node (ref "R19") (pin "1") (pinfunction "1_1") (pintype "passive"))
      (node (ref "R21") (pin "1") (pinfunction "1_1") (pintype "passive"))
      (node (ref "R23") (pin "1") (pinfunction "1_1") (pintype "passive"))
      (node (ref "R24") (pin "2") (pinfunction "2_2") (pintype "passive"))
    )
    (net (code "27") (name "Net-(IC2-PA0{slash}XIN32{slash}EIC{slash}SCOM1PAD0{slash}TC2)") (class "Default")
      (node (ref "C15") (pin "2") (pinfunction "2_2") (pintype "passive"))
      (node (ref "IC2") (pin "1") (pinfunction "PA0/XIN32/EIC/SCOM1PAD0/TC2_1") (pintype "bidirectional"))
      (node (ref "U$19") (pin "P$2") (pinfunction "2_P$2") (pintype "passive"))
    )
    (net (code "28") (name "Net-(IC2-PA1{slash}XOUT32{slash}EIC{slash}SCOM1PAD1{slash}TC2)") (class "Default")
      (node (ref "C4") (pin "1") (pinfunction "1_1") (pintype "passive"))
      (node (ref "IC2") (pin "2") (pinfunction "PA1/XOUT32/EIC/SCOM1PAD1/TC2_2") (pintype "bidirectional"))
      (node (ref "U$19") (pin "P$1") (pinfunction "1_P$1") (pintype "passive"))
    )
    (net (code "29") (name "Net-(IC2-PA12{slash}I2C{slash}EIC{slash}SCOM2PAD0+{slash}TC2)") (class "Default")
      (node (ref "IC2") (pin "21") (pinfunction "PA12/I2C/EIC/SCOM2PAD0+/TC2_21") (pintype "bidirectional"))
      (node (ref "R36") (pin "1") (pinfunction "1_1") (pintype "passive"))
    )
    (net (code "30") (name "Net-(IC2-PA13{slash}I2C{slash}EIC{slash}SCOM2PAD1+{slash}TC2)") (class "Default")
      (node (ref "IC2") (pin "22") (pinfunction "PA13/I2C/EIC/SCOM2PAD1+/TC2_22") (pintype "bidirectional"))
      (node (ref "R50") (pin "1") (pinfunction "1_1") (pintype "passive"))
    )
    (net (code "31") (name "Net-(IC2-PA15{slash}XOUT{slash}EIC{slash}SCOM2PAD3+{slash}TC3)") (class "Default")
      (node (ref "IC2") (pin "24") (pinfunction "PA15/XOUT/EIC/SCOM2PAD3+/TC3_24") (pintype "bidirectional"))
      (node (ref "R11") (pin "1") (pinfunction "1_1") (pintype "passive"))
      (node (ref "U$17") (pin "P$2") (pinfunction "P$2_P$2") (pintype "bidirectional"))
    )
    (net (code "32") (name "Net-(IC2-PA20{slash}EIC{slash}SCOM5PAD2+)") (class "Default")
      (node (ref "IC2") (pin "29") (pinfunction "PA20/EIC/SCOM5PAD2+_29") (pintype "bidirectional"))
      (node (ref "TP10") (pin "TP") (pinfunction "TP_TP") (pintype "input"))
    )
    (net (code "33") (name "Net-(IC2-VDDANA)") (class "Default")
      (node (ref "C106") (pin "1") (pinfunction "1_1") (pintype "passive"))
      (node (ref "C107") (pin "1") (pinfunction "1_1") (pintype "passive"))
      (node (ref "IC2") (pin "6") (pinfunction "VDDANA_6") (pintype "power_in"))
      (node (ref "L100") (pin "1") (pinfunction "1_1") (pintype "passive"))
    )
    (net (code "34") (name "Net-(JP3-LEFT)") (class "Default")
      (node (ref "C2") (pin "1") (pinfunction "1_1") (pintype "passive"))
      (node (ref "C38") (pin "1") (pinfunction "1_1") (pintype "passive"))
      (node (ref "JP3") (pin "TIP") (pinfunction "LEFT_TIP") (pintype "bidirectional"))
      (node (ref "R20") (pin "1") (pinfunction "1_1") (pintype "passive"))
    )
    (net (code "35") (name "Net-(JP3-PadSLEEVE)") (class "Default")
      (node (ref "JP3") (pin "SLEEVE") (pinfunction "SLEEVE_SLEEVE") (pintype "bidirectional"))
      (node (ref "R24") (pin "1") (pinfunction "1_1") (pintype "passive"))
    )
    (net (code "36") (name "Net-(JP3-RIGHT)") (class "Default")
      (node (ref "C23") (pin "1") (pinfunction "1_1") (pintype "passive"))
      (node (ref "C58") (pin "2") (pinfunction "2_2") (pintype "passive"))
      (node (ref "JP3") (pin "RING") (pinfunction "RIGHT_RING") (pintype "bidirectional"))
      (node (ref "R22") (pin "1") (pinfunction "1_1") (pintype "passive"))
    )
    (net (code "37") (name "Net-(POWER-PadC)") (class "Default")
      (node (ref "POWER") (pin "C") (pinfunction "C_C") (pintype "passive"))
      (node (ref "R30") (pin "2") (pinfunction "2_2") (pintype "passive"))
    )
    (net (code "38") (name "Net-(Q1-D)") (class "Default")
      (node (ref "L1") (pin "2") (pinfunction "2_2") (pintype "passive"))
      (node (ref "Q1") (pin "3") (pinfunction "D_3") (pintype "passive"))
      (node (ref "U$1") (pin "6") (pinfunction "E1_6") (pintype "bidirectional"))
    )
    (net (code "39") (name "Net-(Q1-G)") (class "Default")
      (node (ref "Q1") (pin "1") (pinfunction "G_1") (pintype "passive"))
      (node (ref "R48") (pin "2") (pinfunction "2_2") (pintype "passive"))
      (node (ref "U$1") (pin "4") (pinfunction "C2_4") (pintype "bidirectional"))
    )
    (net (code "40") (name "Net-(TP4-1)") (class "Default")
      (node (ref "TP4") (pin "P$1") (pinfunction "1_P$1") (pintype "bidirectional"))
      (node (ref "U$3") (pin "30") (pinfunction "CLKOUT_30") (pintype "bidirectional"))
    )
    (net (code "41") (name "Net-(U$1-B1)") (class "Default")
      (node (ref "R37") (pin "2") (pinfunction "2_2") (pintype "passive"))
      (node (ref "U$1") (pin "1") (pinfunction "C1_1") (pintype "bidirectional"))
      (node (ref "U$1") (pin "2") (pinfunction "B1_2") (pintype "bidirectional"))
      (node (ref "U$1") (pin "3") (pinfunction "B2_3") (pintype "bidirectional"))
    )
    (net (code "42") (name "Net-(U$3-AFE_~{PDN})") (class "Default")
      (node (ref "R33") (pin "1") (pinfunction "1_1") (pintype "passive"))
      (node (ref "U$3") (pin "20") (pinfunction "AFE_~{PDN}_20") (pintype "bidirectional"))
    )
    (net (code "43") (name "Net-(U$3-BG)") (class "Default")
      (node (ref "C8") (pin "1") (pinfunction "1_1") (pintype "passive"))
      (node (ref "U$3") (pin "7") (pinfunction "BG_7") (pintype "bidirectional"))
    )
    (net (code "44") (name "Net-(U$3-INN)") (class "Default")
      (node (ref "R38") (pin "1") (pinfunction "1_1") (pintype "passive"))
      (node (ref "U$3") (pin "1") (pinfunction "INN_1") (pintype "bidirectional"))
    )
    (net (code "45") (name "Net-(U$3-INP)") (class "Default")
      (node (ref "R39") (pin "1") (pinfunction "1_1") (pintype "passive"))
      (node (ref "U$3") (pin "2") (pinfunction "INP_2") (pintype "bidirectional"))
    )
    (net (code "46") (name "Net-(U$3-TXN)") (class "Default")
      (node (ref "R40") (pin "1") (pinfunction "1_1") (pintype "passive"))
      (node (ref "U$3") (pin "14") (pinfunction "TXN_14") (pintype "bidirectional"))
    )
    (net (code "47") (name "Net-(U$3-TXP)") (class "Default")
      (node (ref "R41") (pin "1") (pinfunction "1_1") (pintype "passive"))
      (node (ref "U$3") (pin "15") (pinfunction "TXP_15") (pintype "bidirectional"))
    )
    (net (code "48") (name "Net-(U$3-XIN)") (class "Default")
      (node (ref "C6") (pin "2") (pinfunction "2_2") (pintype "passive"))
      (node (ref "U$3") (pin "38") (pinfunction "XIN_38") (pintype "bidirectional"))
      (node (ref "U$4") (pin "2") (pinfunction "2_2") (pintype "passive"))
    )
    (net (code "49") (name "Net-(U$3-XOUT)") (class "Default")
      (node (ref "C7") (pin "2") (pinfunction "2_2") (pintype "passive"))
      (node (ref "U$3") (pin "37") (pinfunction "XOUT_37") (pintype "bidirectional"))
      (node (ref "U$4") (pin "1") (pinfunction "1_1") (pintype "passive"))
    )
    (net (code "50") (name "Net-(U$8-IN1N)") (class "Default")
      (node (ref "C40") (pin "2") (pinfunction "2_2") (pintype "passive"))
      (node (ref "R12") (pin "2") (pinfunction "2_2") (pintype "passive"))
      (node (ref "R15") (pin "2") (pinfunction "2_2") (pintype "passive"))
      (node (ref "U$8") (pin "3") (pinfunction "IN1N_3") (pintype "input"))
    )
    (net (code "51") (name "Net-(U$8-IN1P)") (class "Default")
      (node (ref "C25") (pin "2") (pinfunction "2_2") (pintype "passive"))
      (node (ref "R16") (pin "2") (pinfunction "2_2") (pintype "passive"))
      (node (ref "R18") (pin "2") (pinfunction "2_2") (pintype "passive"))
      (node (ref "U$8") (pin "4") (pinfunction "IN1P_4") (pintype "input"))
    )
    (net (code "52") (name "Net-(U$8-IN2N)") (class "Default")
      (node (ref "R20") (pin "2") (pinfunction "2_2") (pintype "passive"))
      (node (ref "U$8") (pin "5") (pinfunction "IN2N_5") (pintype "input"))
    )
    (net (code "53") (name "Net-(U$8-IN2P)") (class "Default")
      (node (ref "R22") (pin "2") (pinfunction "2_2") (pintype "passive"))
      (node (ref "U$8") (pin "6") (pinfunction "IN2P_6") (pintype "input"))
    )
    (net (code "54") (name "Net-(U$8-PGA1N)") (class "Default")
      (node (ref "C57") (pin "1") (pinfunction "1_1") (pintype "passive"))
      (node (ref "U$8") (pin "1") (pinfunction "PGA1N_1") (pintype "bidirectional"))
    )
    (net (code "55") (name "Net-(U$8-PGA1P)") (class "Default")
      (node (ref "C57") (pin "2") (pinfunction "2_2") (pintype "passive"))
      (node (ref "U$8") (pin "2") (pinfunction "PGA1P_2") (pintype "bidirectional"))
    )
    (net (code "56") (name "Net-(U$8-PGA2N)") (class "Default")
      (node (ref "C56") (pin "1") (pinfunction "1_1") (pintype "passive"))
      (node (ref "U$8") (pin "7") (pinfunction "PGA2N_7") (pintype "bidirectional"))
    )
    (net (code "57") (name "Net-(U$8-PGA2P)") (class "Default")
      (node (ref "C56") (pin "2") (pinfunction "2_2") (pintype "passive"))
      (node (ref "U$8") (pin "8") (pinfunction "PGA2P_8") (pintype "bidirectional"))
    )
    (net (code "58") (name "Net-(U$8-RESP_MODN)") (class "Default")
      (node (ref "R10") (pin "2") (pinfunction "2_2") (pintype "passive"))
      (node (ref "U$8") (pin "32") (pinfunction "RESP_MODN_32") (pintype "bidirectional"))
    )
    (net (code "59") (name "Net-(U$8-RESP_MODP)") (class "Default")
      (node (ref "R4") (pin "2") (pinfunction "2_2") (pintype "passive"))
      (node (ref "U$8") (pin "31") (pinfunction "RESP_MODP_31") (pintype "bidirectional"))
    )
    (net (code "60") (name "Net-(U$8-RLDINV)") (class "Default")
      (node (ref "C62") (pin "2") (pinfunction "2_2") (pintype "passive"))
      (node (ref "R19") (pin "2") (pinfunction "2_2") (pintype "passive"))
      (node (ref "U$8") (pin "28") (pinfunction "RLDINV_28") (pintype "bidirectional"))
    )
    (net (code "61") (name "Net-(U$8-RLDIN{slash}RLDREF)") (class "Default")
      (node (ref "R21") (pin "2") (pinfunction "2_2") (pintype "passive"))
      (node (ref "U$8") (pin "29") (pinfunction "RLDIN/RLDREF_29") (pintype "bidirectional"))
    )
    (net (code "62") (name "Net-(U$8-RLDOUT)") (class "Default")
      (node (ref "R23") (pin "2") (pinfunction "2_2") (pintype "passive"))
      (node (ref "U$8") (pin "30") (pinfunction "RLDOUT_30") (pintype "bidirectional"))
    )
    (net (code "63") (name "Net-(U$8-VCAP1)") (class "Default")
      (node (ref "C49") (pin "2") (pinfunction "2_2") (pintype "passive"))
      (node (ref "U$8") (pin "11") (pinfunction "VCAP1_11") (pintype "bidirectional"))
    )
    (net (code "64") (name "Net-(U$8-VCAP2)") (class "Default")
      (node (ref "C48") (pin "2") (pinfunction "2_2") (pintype "passive"))
      (node (ref "U$8") (pin "27") (pinfunction "VCAP2_27") (pintype "bidirectional"))
    )
    (net (code "65") (name "Net-(U$8-VREFP)") (class "Default")
      (node (ref "C50") (pin "2") (pinfunction "2_2") (pintype "passive"))
      (node (ref "C51") (pin "1") (pinfunction "1_1") (pintype "passive"))
      (node (ref "U$8") (pin "9") (pinfunction "VREFP_9") (pintype "bidirectional"))
    )
    (net (code "66") (name "Net-(U1-SCL)") (class "Default")
      (node (ref "K1") (pin "28") (pinfunction "28_28") (pintype "passive"))
      (node (ref "R1") (pin "1") (pinfunction "1_1") (pintype "passive"))
      (node (ref "U1") (pin "6") (pinfunction "SCL_6") (pintype "input"))
    )
    (net (code "67") (name "Net-(U1-SDA)") (class "Default")
      (node (ref "K1") (pin "27") (pinfunction "27_27") (pintype "passive"))
      (node (ref "R2") (pin "1") (pinfunction "1_1") (pintype "passive"))
      (node (ref "U1") (pin "5") (pinfunction "SDA_5") (pintype "bidirectional"))
    )
    (net (code "68") (name "Net-(U1-WP)") (class "Default")
      (node (ref "R3") (pin "1") (pinfunction "1_1") (pintype "passive"))
      (node (ref "TP3") (pin "TP") (pinfunction "TP_TP") (pintype "input"))
      (node (ref "U1") (pin "7") (pinfunction "WP_7") (pintype "input"))
    )
    (net (code "69") (name "PD_ALM") (class "Default")
      (node (ref "IC2") (pin "19") (pinfunction "PB10/EIC/SCOM4PAD2/TC5_19") (pintype "bidirectional"))
      (node (ref "TP9") (pin "P$1") (pinfunction "1_P$1") (pintype "bidirectional"))
      (node (ref "U$3") (pin "23") (pinfunction "PD_ALM_23") (pintype "bidirectional"))
    )
    (net (code "70") (name "RPI_RXD") (class "Default")
      (node (ref "K1") (pin "10") (pinfunction "10_10") (pintype "passive"))
      (node (ref "R36") (pin "2") (pinfunction "2_2") (pintype "passive"))
    )
    (net (code "71") (name "RPI_TXD") (class "Default")
      (node (ref "K1") (pin "8") (pinfunction "8_8") (pintype "passive"))
      (node (ref "R50") (pin "2") (pinfunction "2_2") (pintype "passive"))
    )
    (net (code "72") (name "RX_ANA_SUP") (class "Default")
      (node (ref "C11") (pin "1") (pinfunction "1_1") (pintype "passive"))
      (node (ref "C18") (pin "1") (pinfunction "1_1") (pintype "passive"))
      (node (ref "D2") (pin "3") (pinfunction "A_3") (pintype "passive"))
      (node (ref "D3") (pin "3") (pinfunction "A_3") (pintype "passive"))
      (node (ref "U$3") (pin "33") (pinfunction "RX_ANA_SUP_33") (pintype "bidirectional"))
      (node (ref "U$3") (pin "39") (pinfunction "RX_ANA_SUP_39") (pintype "bidirectional"))
      (node (ref "U$7") (pin "2") (pinfunction "P$2_2") (pintype "bidirectional"))
    )
    (net (code "73") (name "RX_DIG_SUP") (class "Default")
      (node (ref "C12") (pin "1") (pinfunction "1_1") (pintype "passive"))
      (node (ref "C19") (pin "1") (pinfunction "1_1") (pintype "passive"))
      (node (ref "R47") (pin "1") (pinfunction "1_1") (pintype "passive"))
      (node (ref "U$3") (pin "31") (pinfunction "RX_DIG_SUP_31") (pintype "bidirectional"))
      (node (ref "U$9") (pin "2") (pinfunction "P$2_2") (pintype "bidirectional"))
    )
    (net (code "74") (name "SAM_RESETN") (class "Default")
      (node (ref "CON_JTAG1") (pin "10") (pinfunction "10_10") (pintype "bidirectional"))
      (node (ref "IC2") (pin "40") (pinfunction "RESETN_40") (pintype "bidirectional"))
      (node (ref "R9") (pin "2") (pinfunction "2_2") (pintype "passive"))
      (node (ref "U$18") (pin "P$1") (pinfunction "P$1_P$1") (pintype "bidirectional"))
    )
    (net (code "75") (name "SAM_SWDCLK") (class "Default")
      (node (ref "CON_JTAG1") (pin "4") (pinfunction "4_4") (pintype "bidirectional"))
      (node (ref "IC2") (pin "45") (pinfunction "PA30/EIC/SCOM1PAD2/TC1_45") (pintype "bidirectional"))
    )
    (net (code "76") (name "SAM_SWDIO") (class "Default")
      (node (ref "CON_JTAG1") (pin "2") (pinfunction "2_2") (pintype "bidirectional"))
      (node (ref "IC2") (pin "46") (pinfunction "PA31/EIC/SCOM1PAD3/TC1_46") (pintype "bidirectional"))
    )
    (net (code "77") (name "SCL") (class "Default")
      (node (ref "IC2") (pin "32") (pinfunction "PA23/I2C/EIC/SCOM5PAD1+/TC4_32") (pintype "bidirectional"))
      (node (ref "R35") (pin "2") (pinfunction "2_2") (pintype "passive"))
      (node (ref "TP1") (pin "TP") (pinfunction "TP_TP") (pintype "input"))
    )
    (net (code "78") (name "SDA") (class "Default")
      (node (ref "IC2") (pin "31") (pinfunction "PA22/I2C/EIC/SCOM5PAD0+/TC4_31") (pintype "bidirectional"))
      (node (ref "R34") (pin "2") (pinfunction "2_2") (pintype "passive"))
      (node (ref "TP2") (pin "TP") (pinfunction "TP_TP") (pintype "input"))
    )
    (net (code "79") (name "SPO2_CS") (class "Default")
      (node (ref "IC2") (pin "7") (pinfunction "PB8/EIC/AIN2/SCOM4PAD0/TC4_7") (pintype "bidirectional"))
      (node (ref "U$3") (pin "27") (pinfunction "SPISTE_27") (pintype "bidirectional"))
    )
    (net (code "80") (name "SPO2_DRDY") (class "Default")
      (node (ref "IC2") (pin "3") (pinfunction "PA2/EIC/AIN0_3") (pintype "bidirectional"))
      (node (ref "U$3") (pin "28") (pinfunction "ADC_RDY_28") (pintype "bidirectional"))
    )
    (net (code "81") (name "SPO2_MISO") (class "Default")
      (node (ref "IC2") (pin "9") (pinfunction "PA4/EIC/REF/AIN4/SCOM0PAD0/TC0_9") (pintype "bidirectional"))
      (node (ref "U$3") (pin "25") (pinfunction "SPISOMI_25") (pintype "bidirectional"))
    )
    (net (code "82") (name "SPO2_MOSI") (class "Default")
      (node (ref "IC2") (pin "11") (pinfunction "PA6/EIC/AIN6/SCOM0PAD2/TC1_11") (pintype "bidirectional"))
      (node (ref "U$3") (pin "26") (pinfunction "SPISIMO_26") (pintype "bidirectional"))
    )
    (net (code "83") (name "SPO2_SCK") (class "Default")
      (node (ref "IC2") (pin "12") (pinfunction "PA7/EIC/AIN7/SCOM0PAD3/TC1_12") (pintype "bidirectional"))
      (node (ref "U$3") (pin "24") (pinfunction "SCLK_24") (pintype "bidirectional"))
    )
    (net (code "84") (name "SPO2_START") (class "Default")
      (node (ref "IC2") (pin "8") (pinfunction "PB9/EIC/AIN3/SCOM4PAD1//TC4_8") (pintype "bidirectional"))
      (node (ref "R33") (pin "2") (pinfunction "2_2") (pintype "passive"))
    )
    (net (code "85") (name "TARGET_USB_N") (class "Default")
      (node (ref "IC2") (pin "33") (pinfunction "PA24/EIC/SCOM3PAD2+/TC5_33") (pintype "bidirectional"))
      (node (ref "R14") (pin "1") (pinfunction "1_1") (pintype "passive"))
    )
    (net (code "86") (name "TARGET_USB_P") (class "Default")
      (node (ref "IC2") (pin "34") (pinfunction "PA25/EIC/SCOM3PAD3+/TC5_34") (pintype "bidirectional"))
      (node (ref "R13") (pin "1") (pinfunction "1_1") (pintype "passive"))
    )
    (net (code "87") (name "TXN") (class "Default")
      (node (ref "D1") (pin "1") (pinfunction "CA_1") (pintype "passive"))
      (node (ref "R40") (pin "2") (pinfunction "2_2") (pintype "passive"))
      (node (ref "X1") (pin "3") (pinfunction "3_3") (pintype "passive"))
    )
    (net (code "88") (name "TXP") (class "Default")
      (node (ref "D5") (pin "1") (pinfunction "CA_1") (pintype "passive"))
      (node (ref "R41") (pin "2") (pinfunction "2_2") (pintype "passive"))
      (node (ref "X1") (pin "2") (pinfunction "2_2") (pintype "passive"))
    )
    (net (code "89") (name "TX_CTRL_SUP") (class "Default")
      (node (ref "C27") (pin "1") (pinfunction "1_1") (pintype "passive"))
      (node (ref "C9") (pin "1") (pinfunction "1_1") (pintype "passive"))
      (node (ref "U$10") (pin "2") (pinfunction "P$2_2") (pintype "bidirectional"))
      (node (ref "U$3") (pin "11") (pinfunction "TX_CTRL_SUP_11") (pintype "bidirectional"))
    )
    (net (code "90") (name "USB_N") (class "Default")
      (node (ref "JP5") (pin "2") (pinfunction "D-_2") (pintype "bidirectional"))
      (node (ref "R14") (pin "2") (pinfunction "2_2") (pintype "passive"))
    )
    (net (code "91") (name "USB_P") (class "Default")
      (node (ref "JP5") (pin "3") (pinfunction "D+_3") (pintype "bidirectional"))
      (node (ref "R13") (pin "2") (pinfunction "2_2") (pintype "passive"))
    )
    (net (code "92") (name "VCCIO") (class "Default")
      (node (ref "C3") (pin "1") (pinfunction "1_1") (pintype "passive"))
      (node (ref "JP5") (pin "1") (pinfunction "VCC_1") (pintype "bidirectional"))
      (node (ref "L1") (pin "1") (pinfunction "1_1") (pintype "passive"))
    )
    (net (code "93") (name "VCM") (class "Default")
      (node (ref "R42") (pin "1") (pinfunction "1_1") (pintype "passive"))
      (node (ref "U$3") (pin "4") (pinfunction "VCM_4") (pintype "bidirectional"))
    )
    (net (code "94") (name "VDDCORE") (class "Default")
      (node (ref "C102") (pin "1") (pinfunction "1_1") (pintype "passive"))
      (node (ref "IC2") (pin "43") (pinfunction "VDDCORE1_43") (pintype "input"))
    )
    (net (code "95") (name "unconnected-(CON_JTAG1-Pad6)") (class "Default")
      (node (ref "CON_JTAG1") (pin "6") (pinfunction "6_6") (pintype "bidirectional"))
    )
    (net (code "96") (name "unconnected-(CON_JTAG1-Pad7)") (class "Default")
      (node (ref "CON_JTAG1") (pin "7") (pinfunction "7_7") (pintype "bidirectional"))
    )
    (net (code "97") (name "unconnected-(CON_JTAG1-Pad8)") (class "Default")
      (node (ref "CON_JTAG1") (pin "8") (pinfunction "8_8") (pintype "bidirectional"))
    )
    (net (code "98") (name "unconnected-(IC2-PA3{slash}EIC{slash}REF{slash}AIN1-Pad4)") (class "Default")
      (node (ref "IC2") (pin "4") (pinfunction "PA3/EIC/REF/AIN1_4") (pintype "bidirectional"))
    )
    (net (code "99") (name "unconnected-(IC2-PA14{slash}XIN{slash}EIC{slash}SCOM2PAD2+{slash}TC3-Pad23)") (class "Default")
      (node (ref "IC2") (pin "23") (pinfunction "PA14/XIN/EIC/SCOM2PAD2+/TC3_23") (pintype "bidirectional"))
    )
    (net (code "100") (name "unconnected-(IC2-PA21{slash}EIC{slash}SCOM5PAD3+-Pad30)") (class "Default")
      (node (ref "IC2") (pin "30") (pinfunction "PA21/EIC/SCOM5PAD3+_30") (pintype "bidirectional"))
    )
    (net (code "101") (name "unconnected-(IC2-PA27{slash}EIC-Pad39)") (class "Default")
      (node (ref "IC2") (pin "39") (pinfunction "PA27/EIC_39") (pintype "bidirectional"))
    )
    (net (code "102") (name "unconnected-(IC2-PA28{slash}EIC-Pad41)") (class "Default")
      (node (ref "IC2") (pin "41") (pinfunction "PA28/EIC_41") (pintype "bidirectional"))
    )
    (net (code "103") (name "unconnected-(IC2-PB2{slash}EIC{slash}AIN10{slash}SCOM5PAD0-Pad47)") (class "Default")
      (node (ref "IC2") (pin "47") (pinfunction "PB2/EIC/AIN10/SCOM5PAD0_47") (pintype "bidirectional"))
    )
    (net (code "104") (name "unconnected-(IC2-PB3{slash}EIC{slash}AIN11{slash}SCOM5PAD1-Pad48)") (class "Default")
      (node (ref "IC2") (pin "48") (pinfunction "PB3/EIC/AIN11/SCOM5PAD1_48") (pintype "bidirectional"))
    )
    (net (code "105") (name "unconnected-(K1-Pad1)") (class "Default")
      (node (ref "K1") (pin "1") (pinfunction "1_1") (pintype "passive"))
    )
    (net (code "106") (name "unconnected-(K1-Pad3)") (class "Default")
      (node (ref "K1") (pin "3") (pinfunction "3_3") (pintype "passive"))
    )
    (net (code "107") (name "unconnected-(K1-Pad5)") (class "Default")
      (node (ref "K1") (pin "5") (pinfunction "5_5") (pintype "passive"))
    )
    (net (code "108") (name "unconnected-(K1-Pad7)") (class "Default")
      (node (ref "K1") (pin "7") (pinfunction "7_7") (pintype "passive"))
    )
    (net (code "109") (name "unconnected-(K1-Pad11)") (class "Default")
      (node (ref "K1") (pin "11") (pinfunction "11_11") (pintype "passive"))
    )
    (net (code "110") (name "unconnected-(K1-Pad12)") (class "Default")
      (node (ref "K1") (pin "12") (pinfunction "12_12") (pintype "passive"))
    )
    (net (code "111") (name "unconnected-(K1-Pad13)") (class "Default")
      (node (ref "K1") (pin "13") (pinfunction "13_13") (pintype "passive"))
    )
    (net (code "112") (name "unconnected-(K1-Pad15)") (class "Default")
      (node (ref "K1") (pin "15") (pinfunction "15_15") (pintype "passive"))
    )
    (net (code "113") (name "unconnected-(K1-Pad16)") (class "Default")
      (node (ref "K1") (pin "16") (pinfunction "16_16") (pintype "passive"))
    )
    (net (code "114") (name "unconnected-(K1-Pad17)") (class "Default")
      (node (ref "K1") (pin "17") (pinfunction "17_17") (pintype "passive"))
    )
    (net (code "115") (name "unconnected-(K1-Pad18)") (class "Default")
      (node (ref "K1") (pin "18") (pinfunction "18_18") (pintype "passive"))
    )
    (net (code "116") (name "unconnected-(K1-Pad19)") (class "Default")
      (node (ref "K1") (pin "19") (pinfunction "19_19") (pintype "passive"))
    )
    (net (code "117") (name "unconnected-(K1-Pad21)") (class "Default")
      (node (ref "K1") (pin "21") (pinfunction "21_21") (pintype "passive"))
    )
    (net (code "118") (name "unconnected-(K1-Pad22)") (class "Default")
      (node (ref "K1") (pin "22") (pinfunction "22_22") (pintype "passive"))
    )
    (net (code "119") (name "unconnected-(K1-Pad23)") (class "Default")
      (node (ref "K1") (pin "23") (pinfunction "23_23") (pintype "passive"))
    )
    (net (code "120") (name "unconnected-(K1-Pad24)") (class "Default")
      (node (ref "K1") (pin "24") (pinfunction "24_24") (pintype "passive"))
    )
    (net (code "121") (name "unconnected-(K1-Pad26)") (class "Default")
      (node (ref "K1") (pin "26") (pinfunction "26_26") (pintype "passive"))
    )
    (net (code "122") (name "unconnected-(K1-Pad29)") (class "Default")
      (node (ref "K1") (pin "29") (pinfunction "29_29") (pintype "passive"))
    )
    (net (code "123") (name "unconnected-(K1-Pad31)") (class "Default")
      (node (ref "K1") (pin "31") (pinfunction "31_31") (pintype "passive"))
    )
    (net (code "124") (name "unconnected-(K1-Pad32)") (class "Default")
      (node (ref "K1") (pin "32") (pinfunction "32_32") (pintype "passive"))
    )
    (net (code "125") (name "unconnected-(K1-Pad33)") (class "Default")
      (node (ref "K1") (pin "33") (pinfunction "33_33") (pintype "passive"))
    )
    (net (code "126") (name "unconnected-(K1-Pad35)") (class "Default")
      (node (ref "K1") (pin "35") (pinfunction "35_35") (pintype "passive"))
    )
    (net (code "127") (name "unconnected-(K1-Pad36)") (class "Default")
      (node (ref "K1") (pin "36") (pinfunction "36_36") (pintype "passive"))
    )
    (net (code "128") (name "unconnected-(K1-Pad37)") (class "Default")
      (node (ref "K1") (pin "37") (pinfunction "37_37") (pintype "passive"))
    )
    (net (code "129") (name "unconnected-(K1-Pad38)") (class "Default")
      (node (ref "K1") (pin "38") (pinfunction "38_38") (pintype "passive"))
    )
    (net (code "130") (name "unconnected-(K1-Pad40)") (class "Default")
      (node (ref "K1") (pin "40") (pinfunction "40_40") (pintype "passive"))
    )
    (net (code "131") (name "unconnected-(U$3-DNC-Pad5)") (class "Default")
      (node (ref "U$3") (pin "5") (pinfunction "DNC_5") (pintype "bidirectional"))
    )
    (net (code "132") (name "unconnected-(U$3-DNC-Pad6)") (class "Default")
      (node (ref "U$3") (pin "6") (pinfunction "DNC_6") (pintype "bidirectional"))
    )
    (net (code "133") (name "unconnected-(U$3-DNC-Pad10)") (class "Default")
      (node (ref "U$3") (pin "10") (pinfunction "DNC_10") (pintype "bidirectional"))
    )
    (net (code "134") (name "unconnected-(U$3-DNC-Pad34)") (class "Default")
      (node (ref "U$3") (pin "34") (pinfunction "DNC_34") (pintype "bidirectional"))
    )
    (net (code "135") (name "unconnected-(U$3-DNC-Pad35)") (class "Default")
      (node (ref "U$3") (pin "35") (pinfunction "DNC_35") (pintype "bidirectional"))
    )
    (net (code "136") (name "unconnected-(U$3-RSVD-Pad9)") (class "Default")
      (node (ref "U$3") (pin "9") (pinfunction "RSVD_9") (pintype "bidirectional"))
    )
    (net (code "137") (name "unconnected-(U$8-GPIO1-Pad26)") (class "Default")
      (node (ref "U$8") (pin "26") (pinfunction "GPIO1_26") (pintype "bidirectional"))
    )
    (net (code "138") (name "unconnected-(U$8-GPIO2-Pad25)") (class "Default")
      (node (ref "U$8") (pin "25") (pinfunction "GPIO2_25") (pintype "bidirectional"))
    )
    (net (code "139") (name "unconnected-(U3-BP-Pad4)") (class "Default")
      (node (ref "U3") (pin "4") (pinfunction "BP_4") (pintype "input"))
    )
    (net (code "140") (name "unconnected-(X1-Pad1)") (class "Default")
      (node (ref "X1") (pin "1") (pinfunction "1_1") (pintype "passive"))
    )
    (net (code "141") (name "unconnected-(X1-Pad4)") (class "Default")
      (node (ref "X1") (pin "4") (pinfunction "4_4") (pintype "passive"))
    )
    (net (code "142") (name "unconnected-(X1-Pad6)") (class "Default")
      (node (ref "X1") (pin "6") (pinfunction "6_6") (pintype "passive"))
    )
    (net (code "143") (name "unconnected-(X1-Pad8)") (class "Default")
      (node (ref "X1") (pin "8") (pinfunction "8_8") (pintype "passive"))
    )
    (net (code "144") (name "~{ADC_RESET}") (class "Default")
      (node (ref "R47") (pin "2") (pinfunction "2_2") (pintype "passive"))
      (node (ref "U$3") (pin "29") (pinfunction "~{RESET}_29") (pintype "bidirectional"))
    )
  )
)
